# SCH__-MIDI.net
KiCad netlist of a schematic drawn in EasyEDA
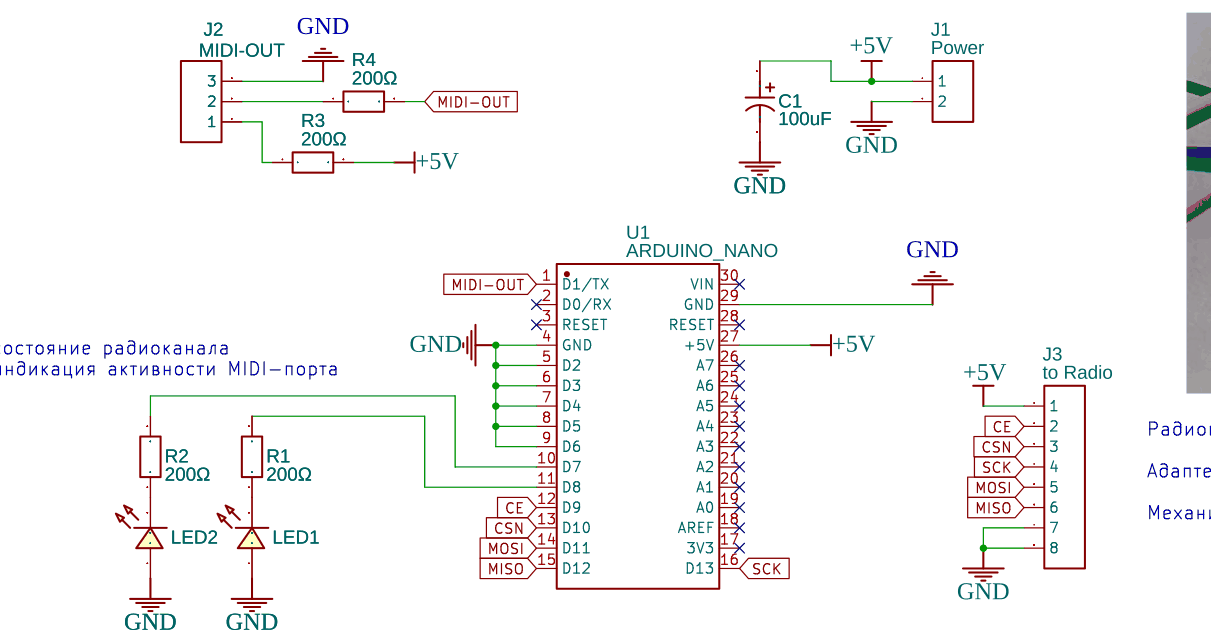
[diagram p0: schematic sheet]

(export (version "E")
  (design (tool "Eeschema 10.0.6"))
  (components
    (comp (ref "C1")
      (value "100uF")
      (fields (field (name "Manufacturer Part") "01EC1385") (field (name "Manufacturer") "KNSCHA(科尼盛)"))
      (libsource (lib "") (part "01EC1385"))
    )
    (comp (ref "J1") (value "Power") (libsource (lib "") (part "HDR-M-2.54_1x2")))
    (comp (ref "J2") (value "MIDI-OUT") (libsource (lib "") (part "HDR-M-2.54_1x3")))
    (comp (ref "J3") (value "to Radio") (libsource (lib "") (part "HDR-M-2.54_1x8")))
    (comp (ref "LED1")
      (value "LED-TH-3mm_R")
      (fields
        (field (name "Manufacturer Part") "204-10SDRD/S530-A3-L")
        (field (name "Manufacturer") "EVERLIGHT(台湾亿光)")
      )
      (libsource (lib "") (part "LED-TH-3mm_R"))
    )
    (comp (ref "LED2")
      (value "LED-TH-3mm_R")
      (fields
        (field (name "Manufacturer Part") "204-10SDRD/S530-A3-L")
        (field (name "Manufacturer") "EVERLIGHT(台湾亿光)")
      )
      (libsource (lib "") (part "LED-TH-3mm_R"))
    )
    (comp (ref "R1")
      (value "200Ω")
      (fields (field (name "Manufacturer Part") "CR1/8W-200Ω±5%-OT52") (field (name "Manufacturer") "VO(翔胜)"))
      (libsource (lib "") (part "CR1/8W-200Ω±5%-OT52"))
    )
    (comp (ref "R2")
      (value "200Ω")
      (fields (field (name "Manufacturer Part") "CR1/8W-200Ω±5%-OT52") (field (name "Manufacturer") "VO(翔胜)"))
      (libsource (lib "") (part "CR1/8W-200Ω±5%-OT52"))
    )
    (comp (ref "R3")
      (value "200Ω")
      (fields (field (name "Manufacturer Part") "CR1/8W-200Ω±5%-OT52") (field (name "Manufacturer") "VO(翔胜)"))
      (libsource (lib "") (part "CR1/8W-200Ω±5%-OT52_1"))
    )
    (comp (ref "R4")
      (value "200Ω")
      (fields (field (name "Manufacturer Part") "CR1/8W-200Ω±5%-OT52") (field (name "Manufacturer") "VO(翔胜)"))
      (libsource (lib "") (part "CR1/8W-200Ω±5%-OT52_1"))
    )
    (comp (ref "U1") (value "ARDUINO_NANO") (libsource (lib "") (part "ARDUINO_NANO")))
  )
  (nets
    (net (code "1") (name "+5V") (class "Default")
      (node (ref "C1") (pin "1") (pinfunction "1_1") (pintype "input"))
      (node (ref "J1") (pin "1") (pinfunction "1_1") (pintype "unspecified"))
      (node (ref "J3") (pin "1") (pinfunction "1_1") (pintype "unspecified"))
      (node (ref "R3") (pin "2") (pinfunction "2_2") (pintype "unspecified"))
      (node (ref "U1") (pin "27") (pinfunction "+5V_27") (pintype "unspecified"))
    )
    (net (code "2") (name "CE") (class "Default")
      (node (ref "J3") (pin "2") (pinfunction "2_2") (pintype "unspecified"))
      (node (ref "U1") (pin "12") (pinfunction "D9_12") (pintype "unspecified"))
    )
    (net (code "3") (name "CSN") (class "Default")
      (node (ref "J3") (pin "3") (pinfunction "3_3") (pintype "unspecified"))
      (node (ref "U1") (pin "13") (pinfunction "D10_13") (pintype "unspecified"))
    )
    (net (code "4") (name "GND") (class "Default")
      (node (ref "C1") (pin "2") (pinfunction "2_2") (pintype "input"))
      (node (ref "J1") (pin "2") (pinfunction "2_2") (pintype "unspecified"))
      (node (ref "J2") (pin "3") (pinfunction "3_3") (pintype "input"))
      (node (ref "J3") (pin "7") (pinfunction "7_7") (pintype "unspecified"))
      (node (ref "J3") (pin "8") (pinfunction "8_8") (pintype "unspecified"))
      (node (ref "LED1") (pin "1") (pinfunction "1_1") (pintype "unspecified"))
      (node (ref "LED2") (pin "1") (pinfunction "1_1") (pintype "unspecified"))
      (node (ref "U1") (pin "29") (pinfunction "GND_29") (pintype "unspecified"))
      (node (ref "U1") (pin "4") (pinfunction "GND_4") (pintype "unspecified"))
      (node (ref "U1") (pin "5") (pinfunction "D2_5") (pintype "unspecified"))
      (node (ref "U1") (pin "6") (pinfunction "D3_6") (pintype "unspecified"))
      (node (ref "U1") (pin "7") (pinfunction "D4_7") (pintype "unspecified"))
      (node (ref "U1") (pin "8") (pinfunction "D5_8") (pintype "unspecified"))
      (node (ref "U1") (pin "9") (pinfunction "D6_9") (pintype "unspecified"))
    )
    (net (code "5") (name "MIDI-OUT") (class "Default")
      (node (ref "R4") (pin "2") (pinfunction "2_2") (pintype "unspecified"))
      (node (ref "U1") (pin "1") (pinfunction "D1/TX_1") (pintype "unspecified"))
    )
    (net (code "6") (name "MISO") (class "Default")
      (node (ref "J3") (pin "6") (pinfunction "6_6") (pintype "unspecified"))
      (node (ref "U1") (pin "15") (pinfunction "D12_15") (pintype "unspecified"))
    )
    (net (code "7") (name "MOSI") (class "Default")
      (node (ref "J3") (pin "5") (pinfunction "5_5") (pintype "unspecified"))
      (node (ref "U1") (pin "14") (pinfunction "D11_14") (pintype "unspecified"))
    )
    (net (code "8") (name "Net-(J2-Pad1)") (class "Default")
      (node (ref "J2") (pin "1") (pinfunction "1_1") (pintype "input"))
      (node (ref "R3") (pin "1") (pinfunction "1_1") (pintype "unspecified"))
    )
    (net (code "9") (name "Net-(J2-Pad2)") (class "Default")
      (node (ref "J2") (pin "2") (pinfunction "2_2") (pintype "input"))
      (node (ref "R4") (pin "1") (pinfunction "1_1") (pintype "unspecified"))
    )
    (net (code "10") (name "Net-(LED1-Pad2)") (class "Default")
      (node (ref "LED1") (pin "2") (pinfunction "2_2") (pintype "unspecified"))
      (node (ref "R1") (pin "1") (pinfunction "1_1") (pintype "unspecified"))
    )
    (net (code "11") (name "Net-(LED2-Pad2)") (class "Default")
      (node (ref "LED2") (pin "2") (pinfunction "2_2") (pintype "unspecified"))
      (node (ref "R2") (pin "1") (pinfunction "1_1") (pintype "unspecified"))
    )
    (net (code "12") (name "Net-(U1-D7)") (class "Default")
      (node (ref "R2") (pin "2") (pinfunction "2_2") (pintype "unspecified"))
      (node (ref "U1") (pin "10") (pinfunction "D7_10") (pintype "unspecified"))
    )
    (net (code "13") (name "Net-(U1-D8)") (class "Default")
      (node (ref "R1") (pin "2") (pinfunction "2_2") (pintype "unspecified"))
      (node (ref "U1") (pin "11") (pinfunction "D8_11") (pintype "unspecified"))
    )
    (net (code "14") (name "SCK") (class "Default")
      (node (ref "J3") (pin "4") (pinfunction "4_4") (pintype "unspecified"))
      (node (ref "U1") (pin "16") (pinfunction "D13_16") (pintype "unspecified"))
    )
    (net (code "15") (name "unconnected-(U1-3V3-Pad17)") (class "Default")
      (node (ref "U1") (pin "17") (pinfunction "3V3_17") (pintype "unspecified+no_connect"))
    )
    (net (code "16") (name "unconnected-(U1-A0-Pad19)") (class "Default")
      (node (ref "U1") (pin "19") (pinfunction "A0_19") (pintype "unspecified+no_connect"))
    )
    (net (code "17") (name "unconnected-(U1-A1-Pad20)") (class "Default")
      (node (ref "U1") (pin "20") (pinfunction "A1_20") (pintype "unspecified+no_connect"))
    )
    (net (code "18") (name "unconnected-(U1-A2-Pad21)") (class "Default")
      (node (ref "U1") (pin "21") (pinfunction "A2_21") (pintype "unspecified+no_connect"))
    )
    (net (code "19") (name "unconnected-(U1-A3-Pad22)") (class "Default")
      (node (ref "U1") (pin "22") (pinfunction "A3_22") (pintype "unspecified+no_connect"))
    )
    (net (code "20") (name "unconnected-(U1-A4-Pad23)") (class "Default")
      (node (ref "U1") (pin "23") (pinfunction "A4_23") (pintype "unspecified+no_connect"))
    )
    (net (code "21") (name "unconnected-(U1-A5-Pad24)") (class "Default")
      (node (ref "U1") (pin "24") (pinfunction "A5_24") (pintype "unspecified+no_connect"))
    )
    (net (code "22") (name "unconnected-(U1-A6-Pad25)") (class "Default")
      (node (ref "U1") (pin "25") (pinfunction "A6_25") (pintype "unspecified+no_connect"))
    )
    (net (code "23") (name "unconnected-(U1-A7-Pad26)") (class "Default")
      (node (ref "U1") (pin "26") (pinfunction "A7_26") (pintype "unspecified+no_connect"))
    )
    (net (code "24") (name "unconnected-(U1-AREF-Pad18)") (class "Default")
      (node (ref "U1") (pin "18") (pinfunction "AREF_18") (pintype "unspecified+no_connect"))
    )
    (net (code "25") (name "unconnected-(U1-D0{slash}RX-Pad2)") (class "Default")
      (node (ref "U1") (pin "2") (pinfunction "D0/RX_2") (pintype "unspecified+no_connect"))
    )
    (net (code "26") (name "unconnected-(U1-RESET-Pad3)") (class "Default")
      (node (ref "U1") (pin "3") (pinfunction "RESET_3") (pintype "unspecified+no_connect"))
    )
    (net (code "27") (name "unconnected-(U1-RESET-Pad28)") (class "Default")
      (node (ref "U1") (pin "28") (pinfunction "RESET_28") (pintype "unspecified+no_connect"))
    )
    (net (code "28") (name "unconnected-(U1-VIN-Pad30)") (class "Default")
      (node (ref "U1") (pin "30") (pinfunction "VIN_30") (pintype "unspecified+no_connect"))
    )
  )
)
